# BBShield.net
KiCad netlist of a schematic drawn in EAGLE
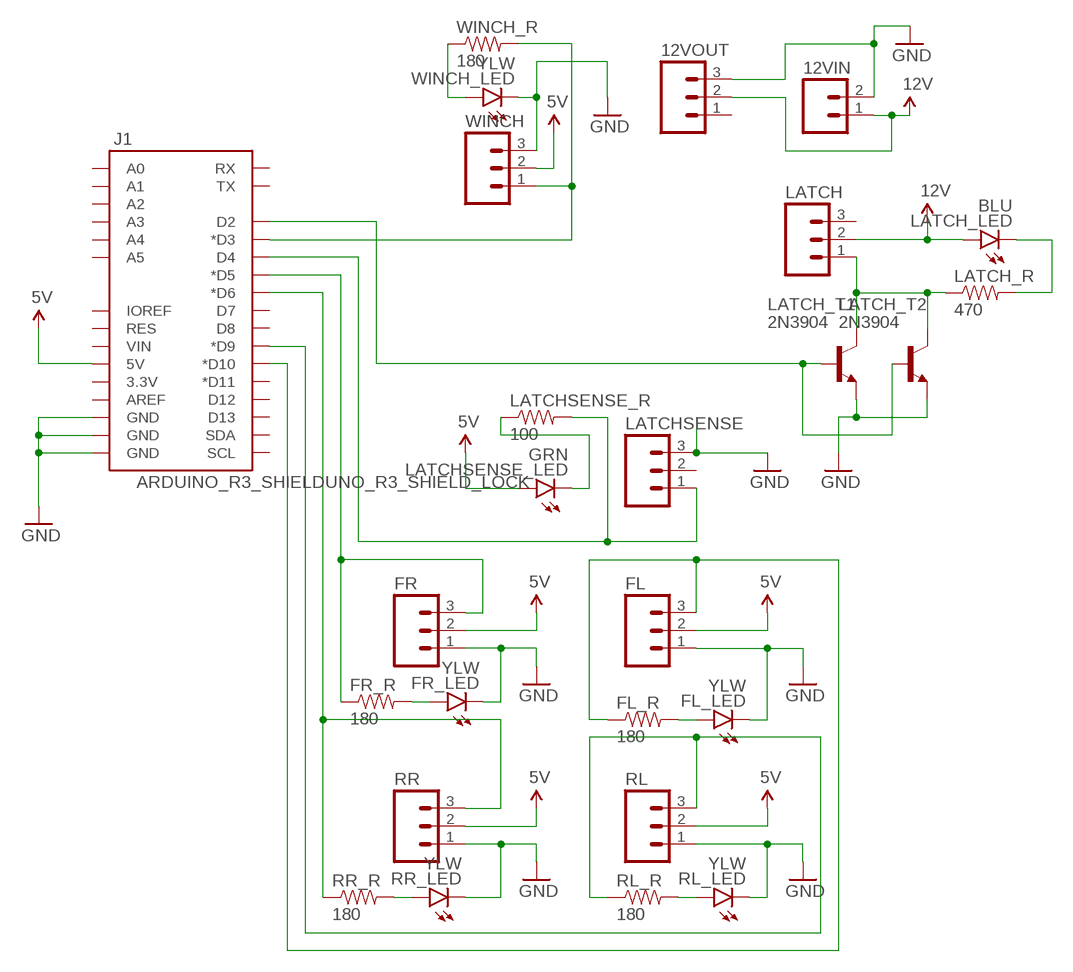
[diagram p0: schematic, sheet 1]

(export (version "E")
  (design (tool "Eeschema 10.0.6"))
  (components
    (comp (ref "12VIN")
      (value "M025MM")
      (footprint "eagle-import:SCREWTERMINAL-5MM-2")
      (libsource (lib "eagle-import") (part "M025MM"))
    )
    (comp (ref "12VOUT")
      (value "M03LOCK")
      (footprint "eagle-import:1X03_LOCK")
      (libsource (lib "eagle-import") (part "M03LOCK"))
    )
    (comp (ref "FL")
      (value "M03LOCK")
      (footprint "eagle-import:1X03_LOCK")
      (libsource (lib "eagle-import") (part "M03LOCK"))
    )
    (comp (ref "FL_LED")
      (value "YLW")
      (footprint "eagle-import:LED3MM")
      (libsource (lib "eagle-import") (part "LED3MM"))
    )
    (comp (ref "FL_R")
      (value "180")
      (footprint "eagle-import:AXIAL-0.4")
      (libsource (lib "eagle-import") (part "RESISTORPTH-1/4W"))
    )
    (comp (ref "FR")
      (value "M03LOCK")
      (footprint "eagle-import:1X03_LOCK")
      (libsource (lib "eagle-import") (part "M03LOCK"))
    )
    (comp (ref "FR_LED")
      (value "YLW")
      (footprint "eagle-import:LED3MM")
      (libsource (lib "eagle-import") (part "LED3MM"))
    )
    (comp (ref "FR_R")
      (value "180")
      (footprint "eagle-import:AXIAL-0.4")
      (libsource (lib "eagle-import") (part "RESISTORPTH-1/4W"))
    )
    (comp (ref "J1")
      (value "ARDUINO_R3_SHIELDUNO_R3_SHIELD_LOCK")
      (footprint "eagle-import:UNO_R3_SHIELD_LOCK")
      (libsource (lib "eagle-import") (part "ARDUINO_R3_SHIELDUNO_R3_SHIELD_LOCK"))
    )
    (comp (ref "LATCH")
      (value "M03LOCK")
      (footprint "eagle-import:1X03_LOCK")
      (libsource (lib "eagle-import") (part "M03LOCK"))
    )
    (comp (ref "LATCHSENSE")
      (value "M03LOCK")
      (footprint "eagle-import:1X03_LOCK")
      (libsource (lib "eagle-import") (part "M03LOCK"))
    )
    (comp (ref "LATCHSENSE_LED")
      (value "GRN")
      (footprint "eagle-import:LED3MM")
      (libsource (lib "eagle-import") (part "LED3MM"))
    )
    (comp (ref "LATCHSENSE_R")
      (value "100")
      (footprint "eagle-import:AXIAL-0.4")
      (libsource (lib "eagle-import") (part "RESISTORPTH-1/4W"))
    )
    (comp (ref "LATCH_LED")
      (value "BLU")
      (footprint "eagle-import:LED3MM")
      (libsource (lib "eagle-import") (part "LED3MM"))
    )
    (comp (ref "LATCH_R")
      (value "470")
      (footprint "eagle-import:AXIAL-0.4")
      (libsource (lib "eagle-import") (part "RESISTORPTH-1/4W"))
    )
    (comp (ref "LATCH_T1")
      (value "2N3904")
      (footprint "eagle-import:TO92")
      (libsource (lib "eagle-import") (part "2N3904"))
    )
    (comp (ref "LATCH_T2")
      (value "2N3904")
      (footprint "eagle-import:TO92")
      (libsource (lib "eagle-import") (part "2N3904"))
    )
    (comp (ref "RL")
      (value "M03LOCK")
      (footprint "eagle-import:1X03_LOCK")
      (libsource (lib "eagle-import") (part "M03LOCK"))
    )
    (comp (ref "RL_LED")
      (value "YLW")
      (footprint "eagle-import:LED3MM")
      (libsource (lib "eagle-import") (part "LED3MM"))
    )
    (comp (ref "RL_R")
      (value "180")
      (footprint "eagle-import:AXIAL-0.4")
      (libsource (lib "eagle-import") (part "RESISTORPTH-1/4W"))
    )
    (comp (ref "RR")
      (value "M03LOCK")
      (footprint "eagle-import:1X03_LOCK")
      (libsource (lib "eagle-import") (part "M03LOCK"))
    )
    (comp (ref "RR_LED")
      (value "YLW")
      (footprint "eagle-import:LED3MM")
      (libsource (lib "eagle-import") (part "LED3MM"))
    )
    (comp (ref "RR_R")
      (value "180")
      (footprint "eagle-import:AXIAL-0.4")
      (libsource (lib "eagle-import") (part "RESISTORPTH-1/4W"))
    )
    (comp (ref "WINCH")
      (value "M03LOCK")
      (footprint "eagle-import:1X03_LOCK")
      (libsource (lib "eagle-import") (part "M03LOCK"))
    )
    (comp (ref "WINCH_LED")
      (value "YLW")
      (footprint "eagle-import:LED3MM")
      (libsource (lib "eagle-import") (part "LED3MM"))
    )
    (comp (ref "WINCH_R")
      (value "180")
      (footprint "eagle-import:AXIAL-0.4")
      (libsource (lib "eagle-import") (part "RESISTORPTH-1/4W"))
    )
  )
  (nets
    (net (code "1") (name "5V") (class "Default")
      (node (ref "FL") (pin "2") (pinfunction "2_2") (pintype "passive"))
      (node (ref "FR") (pin "2") (pinfunction "2_2") (pintype "passive"))
      (node (ref "J1") (pin "5V") (pinfunction "5V_5V") (pintype "bidirectional"))
      (node (ref "LATCHSENSE_LED") (pin "A") (pinfunction "A_A") (pintype "passive"))
      (node (ref "RL") (pin "2") (pinfunction "2_2") (pintype "passive"))
      (node (ref "RR") (pin "2") (pinfunction "2_2") (pintype "passive"))
      (node (ref "WINCH") (pin "2") (pinfunction "2_2") (pintype "passive"))
    )
    (net (code "2") (name "12V") (class "Default")
      (node (ref "12VIN") (pin "1") (pinfunction "1_1") (pintype "passive"))
      (node (ref "12VOUT") (pin "2") (pinfunction "2_2") (pintype "passive"))
      (node (ref "LATCH") (pin "2") (pinfunction "2_2") (pintype "passive"))
      (node (ref "LATCH_LED") (pin "A") (pinfunction "A_A") (pintype "passive"))
    )
    (net (code "3") (name "GND") (class "Default")
      (node (ref "12VIN") (pin "2") (pinfunction "2_2") (pintype "passive"))
      (node (ref "12VOUT") (pin "3") (pinfunction "3_3") (pintype "passive"))
      (node (ref "FL") (pin "1") (pinfunction "1_1") (pintype "passive"))
      (node (ref "FL_LED") (pin "K") (pinfunction "C_K") (pintype "passive"))
      (node (ref "FR") (pin "1") (pinfunction "1_1") (pintype "passive"))
      (node (ref "FR_LED") (pin "K") (pinfunction "C_K") (pintype "passive"))
      (node (ref "J1") (pin "GND@0") (pinfunction "GND_GND@0") (pintype "bidirectional"))
      (node (ref "J1") (pin "GND@1") (pinfunction "GND_GND@1") (pintype "bidirectional"))
      (node (ref "J1") (pin "GND@2") (pinfunction "GND_GND@2") (pintype "bidirectional"))
      (node (ref "LATCHSENSE") (pin "3") (pinfunction "3_3") (pintype "passive"))
      (node (ref "LATCH_T1") (pin "3") (pinfunction "E_3") (pintype "passive"))
      (node (ref "LATCH_T2") (pin "3") (pinfunction "E_3") (pintype "passive"))
      (node (ref "RL") (pin "1") (pinfunction "1_1") (pintype "passive"))
      (node (ref "RL_LED") (pin "K") (pinfunction "C_K") (pintype "passive"))
      (node (ref "RR") (pin "1") (pinfunction "1_1") (pintype "passive"))
      (node (ref "RR_LED") (pin "K") (pinfunction "C_K") (pintype "passive"))
      (node (ref "WINCH") (pin "3") (pinfunction "3_3") (pintype "passive"))
      (node (ref "WINCH_LED") (pin "K") (pinfunction "C_K") (pintype "passive"))
    )
    (net (code "4") (name "Net-(FL_R-1)") (class "Default")
      (node (ref "FL") (pin "3") (pinfunction "3_3") (pintype "passive"))
      (node (ref "FL_R") (pin "P$1") (pinfunction "1_P$1") (pintype "passive"))
      (node (ref "J1") (pin "D10") (pinfunction "*D10_D10") (pintype "bidirectional"))
    )
    (net (code "5") (name "Net-(FL_R-2)") (class "Default")
      (node (ref "FL_LED") (pin "A") (pinfunction "A_A") (pintype "passive"))
      (node (ref "FL_R") (pin "P$2") (pinfunction "2_P$2") (pintype "passive"))
    )
    (net (code "6") (name "Net-(FR_R-1)") (class "Default")
      (node (ref "FR") (pin "3") (pinfunction "3_3") (pintype "passive"))
      (node (ref "FR_R") (pin "P$1") (pinfunction "1_P$1") (pintype "passive"))
      (node (ref "J1") (pin "D5") (pinfunction "*D5_D5") (pintype "bidirectional"))
    )
    (net (code "7") (name "Net-(FR_R-2)") (class "Default")
      (node (ref "FR_LED") (pin "A") (pinfunction "A_A") (pintype "passive"))
      (node (ref "FR_R") (pin "P$2") (pinfunction "2_P$2") (pintype "passive"))
    )
    (net (code "8") (name "Net-(J1-*D3)") (class "Default")
      (node (ref "J1") (pin "D3") (pinfunction "*D3_D3") (pintype "bidirectional"))
      (node (ref "WINCH") (pin "1") (pinfunction "1_1") (pintype "passive"))
      (node (ref "WINCH_R") (pin "P$2") (pinfunction "2_P$2") (pintype "passive"))
    )
    (net (code "9") (name "Net-(J1-*D6)") (class "Default")
      (node (ref "J1") (pin "D6") (pinfunction "*D6_D6") (pintype "bidirectional"))
      (node (ref "RR") (pin "3") (pinfunction "3_3") (pintype "passive"))
      (node (ref "RR_R") (pin "P$1") (pinfunction "1_P$1") (pintype "passive"))
    )
    (net (code "10") (name "Net-(J1-*D9)") (class "Default")
      (node (ref "J1") (pin "D9") (pinfunction "*D9_D9") (pintype "bidirectional"))
      (node (ref "RL") (pin "3") (pinfunction "3_3") (pintype "passive"))
      (node (ref "RL_R") (pin "P$1") (pinfunction "1_P$1") (pintype "passive"))
    )
    (net (code "11") (name "Net-(LATCHSENSE_LED-C)") (class "Default")
      (node (ref "LATCHSENSE_LED") (pin "K") (pinfunction "C_K") (pintype "passive"))
      (node (ref "LATCHSENSE_R") (pin "P$1") (pinfunction "1_P$1") (pintype "passive"))
    )
    (net (code "12") (name "Net-(LATCHSENSE_R-2)") (class "Default")
      (node (ref "J1") (pin "D4") (pinfunction "D4_D4") (pintype "bidirectional"))
      (node (ref "LATCHSENSE") (pin "1") (pinfunction "1_1") (pintype "passive"))
      (node (ref "LATCHSENSE_R") (pin "P$2") (pinfunction "2_P$2") (pintype "passive"))
    )
    (net (code "13") (name "Net-(LATCH_LED-C)") (class "Default")
      (node (ref "LATCH_LED") (pin "K") (pinfunction "C_K") (pintype "passive"))
      (node (ref "LATCH_R") (pin "P$2") (pinfunction "2_P$2") (pintype "passive"))
    )
    (net (code "14") (name "Net-(LATCH_R-1)") (class "Default")
      (node (ref "LATCH") (pin "1") (pinfunction "1_1") (pintype "passive"))
      (node (ref "LATCH_R") (pin "P$1") (pinfunction "1_P$1") (pintype "passive"))
      (node (ref "LATCH_T1") (pin "1") (pinfunction "C_1") (pintype "passive"))
      (node (ref "LATCH_T2") (pin "1") (pinfunction "C_1") (pintype "passive"))
    )
    (net (code "15") (name "Net-(LATCH_T1-B)") (class "Default")
      (node (ref "J1") (pin "D2") (pinfunction "D2_D2") (pintype "bidirectional"))
      (node (ref "LATCH_T1") (pin "2") (pinfunction "B_2") (pintype "passive"))
      (node (ref "LATCH_T2") (pin "2") (pinfunction "B_2") (pintype "passive"))
    )
    (net (code "16") (name "Net-(RL_R-2)") (class "Default")
      (node (ref "RL_LED") (pin "A") (pinfunction "A_A") (pintype "passive"))
      (node (ref "RL_R") (pin "P$2") (pinfunction "2_P$2") (pintype "passive"))
    )
    (net (code "17") (name "Net-(RR_R-2)") (class "Default")
      (node (ref "RR_LED") (pin "A") (pinfunction "A_A") (pintype "passive"))
      (node (ref "RR_R") (pin "P$2") (pinfunction "2_P$2") (pintype "passive"))
    )
    (net (code "18") (name "Net-(WINCH_R-1)") (class "Default")
      (node (ref "WINCH_LED") (pin "A") (pinfunction "A_A") (pintype "passive"))
      (node (ref "WINCH_R") (pin "P$1") (pinfunction "1_P$1") (pintype "passive"))
    )
    (net (code "19") (name "unconnected-(12VOUT-Pad1)") (class "Default")
      (node (ref "12VOUT") (pin "1") (pinfunction "1_1") (pintype "passive"))
    )
    (net (code "20") (name "unconnected-(J1-*D11-PadD11)") (class "Default")
      (node (ref "J1") (pin "D11") (pinfunction "*D11_D11") (pintype "bidirectional"))
    )
    (net (code "21") (name "unconnected-(J1-Pad3.3V)") (class "Default")
      (node (ref "J1") (pin "3.3V") (pinfunction "3.3V_3.3V") (pintype "bidirectional"))
    )
    (net (code "22") (name "unconnected-(J1-PadA0)") (class "Default")
      (node (ref "J1") (pin "A0") (pinfunction "A0_A0") (pintype "bidirectional"))
    )
    (net (code "23") (name "unconnected-(J1-PadA1)") (class "Default")
      (node (ref "J1") (pin "A1") (pinfunction "A1_A1") (pintype "bidirectional"))
    )
    (net (code "24") (name "unconnected-(J1-PadA2)") (class "Default")
      (node (ref "J1") (pin "A2") (pinfunction "A2_A2") (pintype "bidirectional"))
    )
    (net (code "25") (name "unconnected-(J1-PadA3)") (class "Default")
      (node (ref "J1") (pin "A3") (pinfunction "A3_A3") (pintype "bidirectional"))
    )
    (net (code "26") (name "unconnected-(J1-PadA4)") (class "Default")
      (node (ref "J1") (pin "A4") (pinfunction "A4_A4") (pintype "bidirectional"))
    )
    (net (code "27") (name "unconnected-(J1-PadA5)") (class "Default")
      (node (ref "J1") (pin "A5") (pinfunction "A5_A5") (pintype "bidirectional"))
    )
    (net (code "28") (name "unconnected-(J1-PadAREF)") (class "Default")
      (node (ref "J1") (pin "AREF") (pinfunction "AREF_AREF") (pintype "bidirectional"))
    )
    (net (code "29") (name "unconnected-(J1-PadD7)") (class "Default")
      (node (ref "J1") (pin "D7") (pinfunction "D7_D7") (pintype "bidirectional"))
    )
    (net (code "30") (name "unconnected-(J1-PadD8)") (class "Default")
      (node (ref "J1") (pin "D8") (pinfunction "D8_D8") (pintype "bidirectional"))
    )
    (net (code "31") (name "unconnected-(J1-PadD12)") (class "Default")
      (node (ref "J1") (pin "D12") (pinfunction "D12_D12") (pintype "bidirectional"))
    )
    (net (code "32") (name "unconnected-(J1-PadD13)") (class "Default")
      (node (ref "J1") (pin "D13") (pinfunction "D13_D13") (pintype "bidirectional"))
    )
    (net (code "33") (name "unconnected-(J1-PadIOREF)") (class "Default")
      (node (ref "J1") (pin "IOREF") (pinfunction "IOREF_IOREF") (pintype "bidirectional"))
    )
    (net (code "34") (name "unconnected-(J1-PadRES)") (class "Default")
      (node (ref "J1") (pin "RES") (pinfunction "RES_RES") (pintype "bidirectional"))
    )
    (net (code "35") (name "unconnected-(J1-PadRX)") (class "Default")
      (node (ref "J1") (pin "RX") (pinfunction "RX_RX") (pintype "bidirectional"))
    )
    (net (code "36") (name "unconnected-(J1-PadSCL)") (class "Default")
      (node (ref "J1") (pin "SCL") (pinfunction "SCL_SCL") (pintype "bidirectional"))
    )
    (net (code "37") (name "unconnected-(J1-PadSDA)") (class "Default")
      (node (ref "J1") (pin "SDA") (pinfunction "SDA_SDA") (pintype "bidirectional"))
    )
    (net (code "38") (name "unconnected-(J1-PadTX)") (class "Default")
      (node (ref "J1") (pin "TX") (pinfunction "TX_TX") (pintype "bidirectional"))
    )
    (net (code "39") (name "unconnected-(J1-PadVIN)") (class "Default")
      (node (ref "J1") (pin "VIN") (pinfunction "VIN_VIN") (pintype "bidirectional"))
    )
    (net (code "40") (name "unconnected-(LATCH-Pad3)") (class "Default")
      (node (ref "LATCH") (pin "3") (pinfunction "3_3") (pintype "passive"))
    )
    (net (code "41") (name "unconnected-(LATCHSENSE-Pad2)") (class "Default")
      (node (ref "LATCHSENSE") (pin "2") (pinfunction "2_2") (pintype "passive"))
    )
  )
)
